# RollerShutterNode_nrf.net
KiCad netlist of a schematic drawn in EAGLE
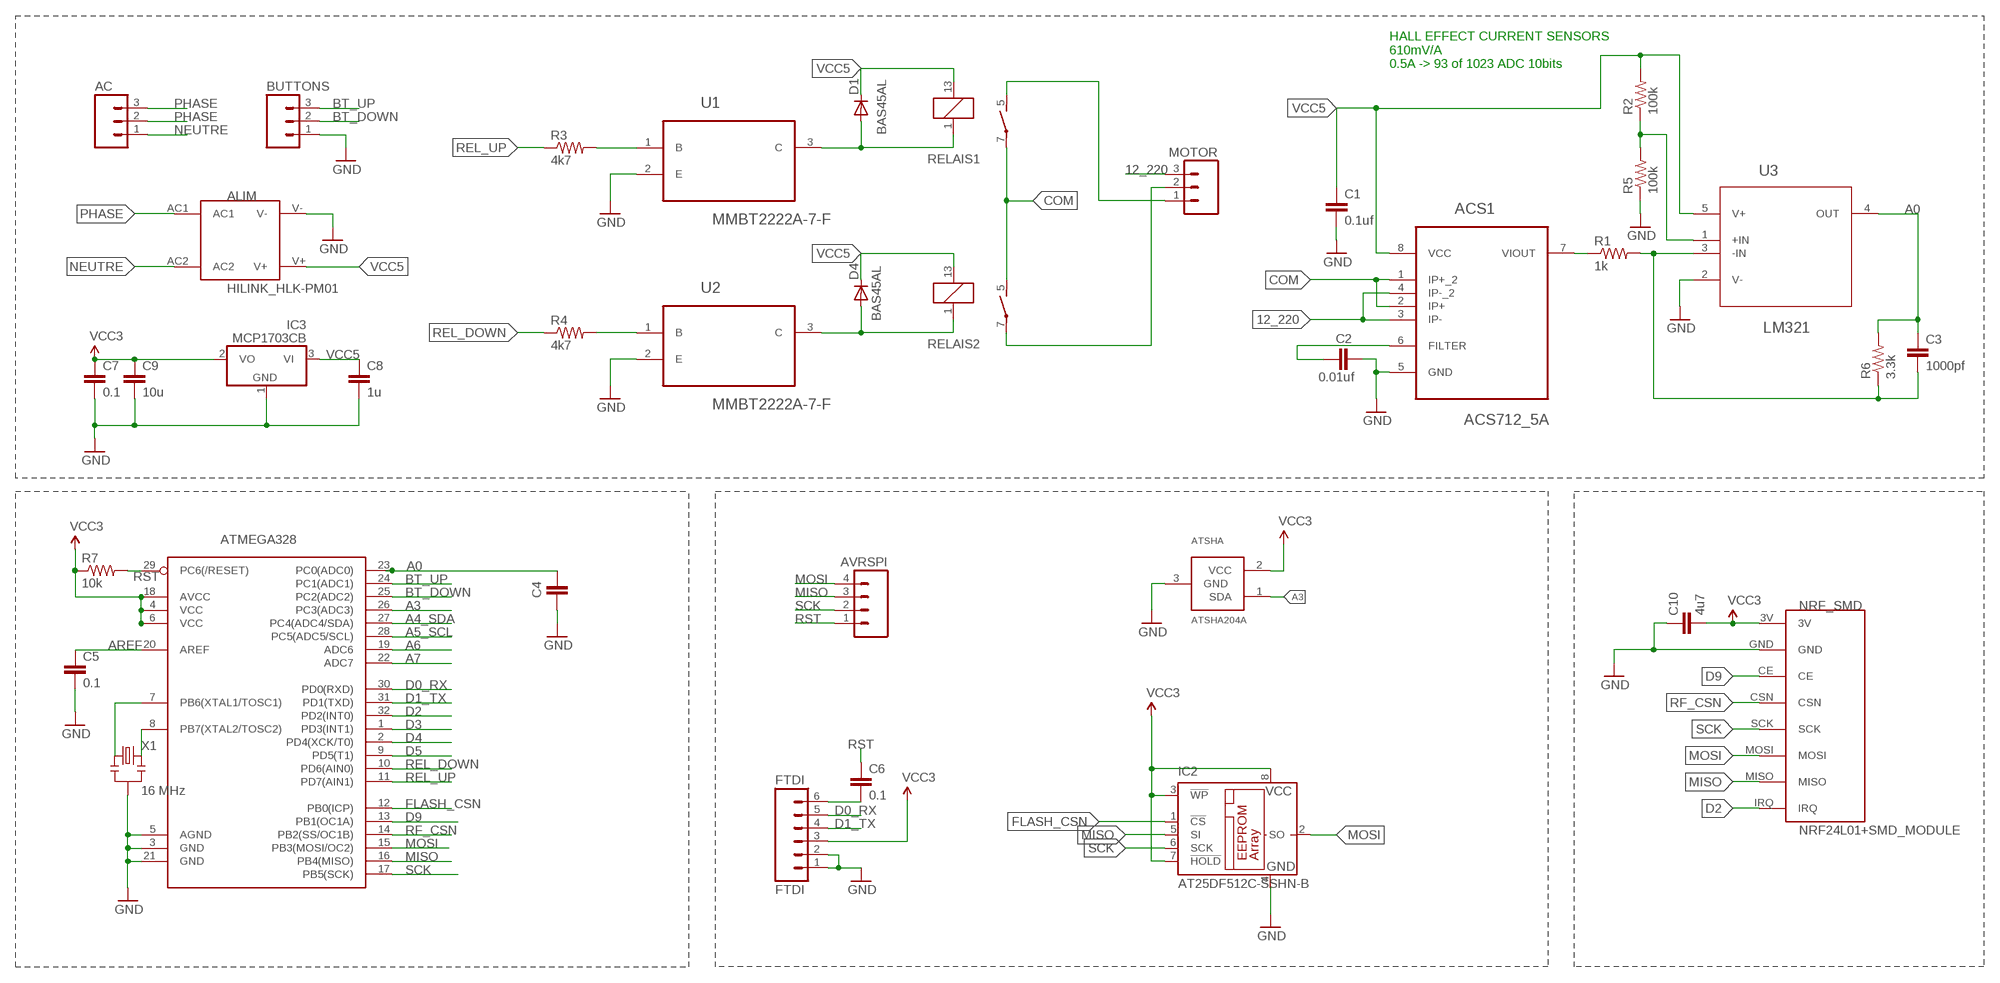
[diagram p0: schematic, sheet 1]

(export (version "E")
  (design (tool "Eeschema 10.0.6"))
  (components
    (comp (ref "AC")
      (value "M03SCREW")
      (footprint "eagle-import:SCREWTERMINAL-3.5MM-3")
      (libsource (lib "eagle-import") (part "M03SCREW"))
    )
    (comp (ref "ACS1")
      (value "ACS712_5A")
      (footprint "eagle-import:SOIC127P600X175-8N")
      (fields (field (name "MPN") "ACS712ELCTR-20A-T"))
      (libsource (lib "eagle-import") (part "ACS712ELCTR-20A-T"))
    )
    (comp (ref "ALIM")
      (value "HILINK_HLK-PM01")
      (footprint "eagle-import:HILINK_HLK-PM01")
      (libsource (lib "eagle-import") (part "HILINK_HLK-PM01"))
    )
    (comp (ref "ATMEGA328")
      (value "ATMega-328")
      (footprint "eagle-import:TQFP32-08")
      (libsource (lib "eagle-import") (part "ATMEGA168/328TQFP32"))
    )
    (comp (ref "ATSHA")
      (value "ATSHA204A")
      (footprint "eagle-import:SOT23")
      (libsource (lib "eagle-import") (part "ATSHA204A"))
    )
    (comp (ref "AVRSPI")
      (value "M04PTH")
      (footprint "eagle-import:1X04")
      (libsource (lib "eagle-import") (part "M04PTH"))
    )
    (comp (ref "BUTTONS")
      (value "M03SCREW")
      (footprint "eagle-import:SCREWTERMINAL-3.5MM-3")
      (libsource (lib "eagle-import") (part "M03SCREW"))
    )
    (comp (ref "C1")
      (value "0.1uf")
      (footprint "eagle-import:0805")
      (libsource (lib "eagle-import") (part "SparkFun-Passives_CAP0805"))
    )
    (comp (ref "C2")
      (value "0.01uf")
      (footprint "eagle-import:0805")
      (libsource (lib "eagle-import") (part "SparkFun-Passives_CAP0805"))
    )
    (comp (ref "C3")
      (value "1000pf")
      (footprint "eagle-import:0805")
      (libsource (lib "eagle-import") (part "SparkFun-Passives_CAP0805"))
    )
    (comp (ref "C4")
      (value "CAP0805")
      (footprint "eagle-import:0805")
      (libsource (lib "eagle-import") (part "SparkFun-Passives_CAP0805"))
    )
    (comp (ref "C5")
      (value "0.1")
      (footprint "eagle-import:0805")
      (libsource (lib "eagle-import") (part "CAP0805"))
    )
    (comp (ref "C6")
      (value "0.1")
      (footprint "eagle-import:0805")
      (libsource (lib "eagle-import") (part "CAP0805"))
    )
    (comp (ref "C7")
      (value "0.1")
      (footprint "eagle-import:0805")
      (libsource (lib "eagle-import") (part "CAP0805"))
    )
    (comp (ref "C8")
      (value "1u")
      (footprint "eagle-import:0805")
      (libsource (lib "eagle-import") (part "CAP0805"))
    )
    (comp (ref "C9")
      (value "10u")
      (footprint "eagle-import:0805-CAP")
      (libsource (lib "eagle-import") (part "CAP0805-CAP"))
    )
    (comp (ref "C10")
      (value "4u7")
      (footprint "eagle-import:0805")
      (libsource (lib "eagle-import") (part "SparkFun-Capacitors_CAP0805"))
    )
    (comp (ref "D1")
      (value "BAS45AL")
      (footprint "eagle-import:SOD80C")
      (libsource (lib "eagle-import") (part "DIODE-SOD80C"))
    )
    (comp (ref "D4")
      (value "BAS45AL")
      (footprint "eagle-import:SOD80C")
      (libsource (lib "eagle-import") (part "DIODE-SOD80C"))
    )
    (comp (ref "FTDI")
      (value "FTDI")
      (footprint "eagle-import:1X06")
      (libsource (lib "eagle-import") (part "M06SIP"))
    )
    (comp (ref "IC2")
      (value "AT25DF512C-SSHN-B")
      (footprint "eagle-import:SO-08")
      (fields (field (name "MF") "MICROCHIP") (field (name "MPN") "25AA080/SN"))
      (libsource (lib "eagle-import") (part "25SNAA080"))
    )
    (comp (ref "IC3")
      (value "MCP1703CB")
      (footprint "eagle-import:SOT23")
      (libsource (lib "eagle-import") (part "MCP1703CB"))
    )
    (comp (ref "MOTOR")
      (value "M03SCREW")
      (footprint "eagle-import:SCREWTERMINAL-3.5MM-3")
      (libsource (lib "eagle-import") (part "M03SCREW"))
    )
    (comp (ref "NRF_SMD")
      (value "NRF24L01+SMD_MODULE")
      (footprint "eagle-import:NRF24L01+SMD_MODULE")
      (libsource (lib "eagle-import") (part "NRF24L01+SMD_MODULE"))
    )
    (comp (ref "R1")
      (value "1k")
      (footprint "eagle-import:0805")
      (libsource (lib "eagle-import") (part "SparkFun-Resistors_RESISTOR0805-RES"))
    )
    (comp (ref "R2")
      (value "100k")
      (footprint "eagle-import:0805")
      (libsource (lib "eagle-import") (part "SparkFun-Resistors_RESISTOR0805-RES"))
    )
    (comp (ref "R3")
      (value "4k7")
      (footprint "eagle-import:0805")
      (libsource (lib "eagle-import") (part "SparkFun-Resistors_RESISTOR0805-RES"))
    )
    (comp (ref "R4")
      (value "4k7")
      (footprint "eagle-import:0805")
      (libsource (lib "eagle-import") (part "SparkFun-Resistors_RESISTOR0805-RES"))
    )
    (comp (ref "R5")
      (value "100k")
      (footprint "eagle-import:0805")
      (libsource (lib "eagle-import") (part "SparkFun-Resistors_RESISTOR0805-RES"))
    )
    (comp (ref "R6")
      (value "3.3k")
      (footprint "eagle-import:0805")
      (libsource (lib "eagle-import") (part "SparkFun-Resistors_RESISTOR0805-RES"))
    )
    (comp (ref "R7")
      (value "10k")
      (footprint "eagle-import:0805")
      (libsource (lib "eagle-import") (part "RESISTOR0805"))
    )
    (comp (ref "RELAIS1")
      (value "Relais G6D")
      (footprint "eagle-import:G6D")
      (libsource (lib "eagle-import") (part "G6D?-1A-ASI12VDC"))
    )
    (comp (ref "RELAIS2")
      (value "Relais G6D")
      (footprint "eagle-import:G6D")
      (libsource (lib "eagle-import") (part "G6D?-1A-ASI12VDC"))
    )
    (comp (ref "U1")
      (value "MMBT2222A-7-F")
      (footprint "eagle-import:SOT103P240X110-3N")
      (libsource (lib "eagle-import") (part "MMBT2222A-7-F"))
    )
    (comp (ref "U2")
      (value "MMBT2222A-7-F")
      (footprint "eagle-import:SOT103P240X110-3N")
      (libsource (lib "eagle-import") (part "MMBT2222A-7-F"))
    )
    (comp (ref "U3")
      (value "LM321")
      (footprint "eagle-import:SOT95P285X120-5N")
      (fields (field (name "MPN") "LM321MF"))
      (libsource (lib "eagle-import") (part "LM321MF"))
    )
    (comp (ref "X1")
      (value "16 MHz")
      (footprint "eagle-import:RESONATOR-SMD")
      (libsource (lib "eagle-import") (part "RESONATORSMD"))
    )
  )
  (nets
    (net (code "1") (name "/A0") (class "Default")
      (node (ref "ATMEGA328") (pin "23") (pinfunction "PC0(ADC0)_23") (pintype "bidirectional"))
      (node (ref "C3") (pin "1") (pinfunction "1_1") (pintype "passive"))
      (node (ref "C4") (pin "2") (pinfunction "2_2") (pintype "passive"))
      (node (ref "R6") (pin "2") (pinfunction "2_2") (pintype "passive"))
      (node (ref "U3") (pin "4") (pinfunction "OUT_4") (pintype "output"))
    )
    (net (code "2") (name "/A4_SDA") (class "Default")
      (node (ref "ATMEGA328") (pin "27") (pinfunction "PC4(ADC4/SDA)_27") (pintype "bidirectional"))
    )
    (net (code "3") (name "/A5_SCL") (class "Default")
      (node (ref "ATMEGA328") (pin "28") (pinfunction "PC5(ADC5/SCL)_28") (pintype "bidirectional"))
    )
    (net (code "4") (name "/A6") (class "Default")
      (node (ref "ATMEGA328") (pin "19") (pinfunction "ADC6_19") (pintype "bidirectional"))
    )
    (net (code "5") (name "/A7") (class "Default")
      (node (ref "ATMEGA328") (pin "22") (pinfunction "ADC7_22") (pintype "bidirectional"))
    )
    (net (code "6") (name "/AREF") (class "Default")
      (node (ref "ATMEGA328") (pin "20") (pinfunction "AREF_20") (pintype "bidirectional"))
      (node (ref "C5") (pin "1") (pinfunction "1_1") (pintype "passive"))
    )
    (net (code "7") (name "/BT_DOWN") (class "Default")
      (node (ref "ATMEGA328") (pin "25") (pinfunction "PC2(ADC2)_25") (pintype "bidirectional"))
      (node (ref "BUTTONS") (pin "2") (pinfunction "2_2") (pintype "passive"))
    )
    (net (code "8") (name "/BT_UP") (class "Default")
      (node (ref "ATMEGA328") (pin "24") (pinfunction "PC1(ADC1)_24") (pintype "bidirectional"))
      (node (ref "BUTTONS") (pin "3") (pinfunction "3_3") (pintype "passive"))
    )
    (net (code "9") (name "/D0_RX") (class "Default")
      (node (ref "ATMEGA328") (pin "30") (pinfunction "PD0(RXD)_30") (pintype "bidirectional"))
      (node (ref "FTDI") (pin "5") (pinfunction "5_5") (pintype "passive"))
    )
    (net (code "10") (name "/D1_TX") (class "Default")
      (node (ref "ATMEGA328") (pin "31") (pinfunction "PD1(TXD)_31") (pintype "bidirectional"))
      (node (ref "FTDI") (pin "4") (pinfunction "4_4") (pintype "passive"))
    )
    (net (code "11") (name "/D3") (class "Default")
      (node (ref "ATMEGA328") (pin "1") (pinfunction "PD3(INT1)_1") (pintype "bidirectional"))
    )
    (net (code "12") (name "/D4") (class "Default")
      (node (ref "ATMEGA328") (pin "2") (pinfunction "PD4(XCK/T0)_2") (pintype "bidirectional"))
    )
    (net (code "13") (name "/D5") (class "Default")
      (node (ref "ATMEGA328") (pin "9") (pinfunction "PD5(T1)_9") (pintype "bidirectional"))
    )
    (net (code "14") (name "/RST") (class "Default")
      (node (ref "ATMEGA328") (pin "29") (pinfunction "PC6(/RESET)_29") (pintype "bidirectional"))
      (node (ref "AVRSPI") (pin "1") (pinfunction "1_1") (pintype "passive"))
      (node (ref "C6") (pin "1") (pinfunction "1_1") (pintype "passive"))
      (node (ref "R7") (pin "2") (pinfunction "2_2") (pintype "passive"))
    )
    (net (code "15") (name "12_220") (class "Default")
      (node (ref "ACS1") (pin "3") (pinfunction "IP-_3") (pintype "input"))
      (node (ref "ACS1") (pin "4") (pinfunction "IP-_2_4") (pintype "input"))
      (node (ref "MOTOR") (pin "3") (pinfunction "3_3") (pintype "passive"))
    )
    (net (code "16") (name "A3") (class "Default")
      (node (ref "ATMEGA328") (pin "26") (pinfunction "PC3(ADC3)_26") (pintype "bidirectional"))
      (node (ref "ATSHA") (pin "1") (pinfunction "SDA_1") (pintype "bidirectional"))
    )
    (net (code "17") (name "COM") (class "Default")
      (node (ref "ACS1") (pin "1") (pinfunction "IP+_2_1") (pintype "input"))
      (node (ref "ACS1") (pin "2") (pinfunction "IP+_2") (pintype "input"))
      (node (ref "RELAIS1") (pin "7") (pinfunction "P_7") (pintype "passive"))
      (node (ref "RELAIS2") (pin "5") (pinfunction "S_5") (pintype "passive"))
    )
    (net (code "18") (name "D2") (class "Default")
      (node (ref "ATMEGA328") (pin "32") (pinfunction "PD2(INT0)_32") (pintype "bidirectional"))
      (node (ref "NRF_SMD") (pin "IRQ") (pinfunction "IRQ_IRQ") (pintype "bidirectional"))
    )
    (net (code "19") (name "D9") (class "Default")
      (node (ref "ATMEGA328") (pin "13") (pinfunction "PB1(OC1A)_13") (pintype "bidirectional"))
      (node (ref "NRF_SMD") (pin "CE") (pinfunction "CE_CE") (pintype "bidirectional"))
    )
    (net (code "20") (name "FLASH_CSN") (class "Default")
      (node (ref "ATMEGA328") (pin "12") (pinfunction "PB0(ICP)_12") (pintype "bidirectional"))
      (node (ref "IC2") (pin "1") (pinfunction "~{CS}_1") (pintype "input"))
    )
    (net (code "21") (name "GND") (class "Default")
      (node (ref "ACS1") (pin "5") (pinfunction "GND_5") (pintype "passive"))
      (node (ref "ALIM") (pin "V-") (pinfunction "V-_V-") (pintype "bidirectional"))
      (node (ref "ATMEGA328") (pin "21") (pinfunction "GND_21") (pintype "bidirectional"))
      (node (ref "ATMEGA328") (pin "3") (pinfunction "GND_3") (pintype "bidirectional"))
      (node (ref "ATMEGA328") (pin "5") (pinfunction "AGND_5") (pintype "bidirectional"))
      (node (ref "ATSHA") (pin "3") (pinfunction "GND_3") (pintype "bidirectional"))
      (node (ref "BUTTONS") (pin "1") (pinfunction "1_1") (pintype "passive"))
      (node (ref "C1") (pin "2") (pinfunction "2_2") (pintype "passive"))
      (node (ref "C10") (pin "1") (pinfunction "1_1") (pintype "passive"))
      (node (ref "C2") (pin "2") (pinfunction "2_2") (pintype "passive"))
      (node (ref "C4") (pin "1") (pinfunction "1_1") (pintype "passive"))
      (node (ref "C5") (pin "2") (pinfunction "2_2") (pintype "passive"))
      (node (ref "C7") (pin "2") (pinfunction "2_2") (pintype "passive"))
      (node (ref "C8") (pin "2") (pinfunction "2_2") (pintype "passive"))
      (node (ref "C9") (pin "2") (pinfunction "2_2") (pintype "passive"))
      (node (ref "FTDI") (pin "1") (pinfunction "1_1") (pintype "passive"))
      (node (ref "FTDI") (pin "2") (pinfunction "2_2") (pintype "passive"))
      (node (ref "IC2") (pin "4") (pinfunction "GND_4") (pintype "power_in"))
      (node (ref "IC3") (pin "1") (pinfunction "GND_1") (pintype "passive"))
      (node (ref "NRF_SMD") (pin "GND") (pinfunction "GND_GND") (pintype "bidirectional"))
      (node (ref "R5") (pin "1") (pinfunction "1_1") (pintype "passive"))
      (node (ref "U1") (pin "2") (pinfunction "E_2") (pintype "passive"))
      (node (ref "U2") (pin "2") (pinfunction "E_2") (pintype "passive"))
      (node (ref "U3") (pin "2") (pinfunction "V-_2") (pintype "power_in"))
      (node (ref "X1") (pin "2") (pinfunction "2_2") (pintype "passive"))
    )
    (net (code "22") (name "MISO") (class "Default")
      (node (ref "ATMEGA328") (pin "16") (pinfunction "PB4(MISO)_16") (pintype "bidirectional"))
      (node (ref "AVRSPI") (pin "3") (pinfunction "3_3") (pintype "passive"))
      (node (ref "IC2") (pin "5") (pinfunction "SI_5") (pintype "input"))
      (node (ref "NRF_SMD") (pin "MISO") (pinfunction "MISO_MISO") (pintype "bidirectional"))
    )
    (net (code "23") (name "MOSI") (class "Default")
      (node (ref "ATMEGA328") (pin "15") (pinfunction "PB3(MOSI/OC2)_15") (pintype "bidirectional"))
      (node (ref "AVRSPI") (pin "4") (pinfunction "4_4") (pintype "passive"))
      (node (ref "IC2") (pin "2") (pinfunction "SO_2") (pintype "bidirectional"))
      (node (ref "NRF_SMD") (pin "MOSI") (pinfunction "MOSI_MOSI") (pintype "bidirectional"))
    )
    (net (code "24") (name "NEUTRE") (class "Default")
      (node (ref "AC") (pin "1") (pinfunction "1_1") (pintype "passive"))
      (node (ref "ALIM") (pin "AC2") (pinfunction "AC2_AC2") (pintype "bidirectional"))
    )
    (net (code "25") (name "Net-(ACS1-FILTER)") (class "Default")
      (node (ref "ACS1") (pin "6") (pinfunction "FILTER_6") (pintype "input"))
      (node (ref "C2") (pin "1") (pinfunction "1_1") (pintype "passive"))
    )
    (net (code "26") (name "Net-(ACS1-VIOUT)") (class "Default")
      (node (ref "ACS1") (pin "7") (pinfunction "VIOUT_7") (pintype "output"))
      (node (ref "R1") (pin "1") (pinfunction "1_1") (pintype "passive"))
    )
    (net (code "27") (name "Net-(ATMEGA328-PB6(XTAL1{slash}TOSC1))") (class "Default")
      (node (ref "ATMEGA328") (pin "7") (pinfunction "PB6(XTAL1/TOSC1)_7") (pintype "bidirectional"))
      (node (ref "X1") (pin "1") (pinfunction "1_1") (pintype "passive"))
    )
    (net (code "28") (name "Net-(ATMEGA328-PB7(XTAL2{slash}TOSC2))") (class "Default")
      (node (ref "ATMEGA328") (pin "8") (pinfunction "PB7(XTAL2/TOSC2)_8") (pintype "bidirectional"))
      (node (ref "X1") (pin "3") (pinfunction "3_3") (pintype "passive"))
    )
    (net (code "29") (name "Net-(C6-Pad2)") (class "Default")
      (node (ref "C6") (pin "2") (pinfunction "2_2") (pintype "passive"))
      (node (ref "FTDI") (pin "6") (pinfunction "6_6") (pintype "passive"))
    )
    (net (code "30") (name "Net-(RELAIS1B-S)") (class "Default")
      (node (ref "MOTOR") (pin "1") (pinfunction "1_1") (pintype "passive"))
      (node (ref "RELAIS1") (pin "5") (pinfunction "S_5") (pintype "passive"))
    )
    (net (code "31") (name "Net-(RELAIS2B-P)") (class "Default")
      (node (ref "MOTOR") (pin "2") (pinfunction "2_2") (pintype "passive"))
      (node (ref "RELAIS2") (pin "7") (pinfunction "P_7") (pintype "passive"))
    )
    (net (code "32") (name "Net-(U1-B)") (class "Default")
      (node (ref "R3") (pin "2") (pinfunction "2_2") (pintype "passive"))
      (node (ref "U1") (pin "1") (pinfunction "B_1") (pintype "input"))
    )
    (net (code "33") (name "Net-(U1-C)") (class "Default")
      (node (ref "D1") (pin "A") (pinfunction "A_A") (pintype "passive"))
      (node (ref "RELAIS1") (pin "1") (pinfunction "1_1") (pintype "passive"))
      (node (ref "U1") (pin "3") (pinfunction "C_3") (pintype "output"))
    )
    (net (code "34") (name "Net-(U2-B)") (class "Default")
      (node (ref "R4") (pin "2") (pinfunction "2_2") (pintype "passive"))
      (node (ref "U2") (pin "1") (pinfunction "B_1") (pintype "input"))
    )
    (net (code "35") (name "Net-(U2-C)") (class "Default")
      (node (ref "D4") (pin "A") (pinfunction "A_A") (pintype "passive"))
      (node (ref "RELAIS2") (pin "1") (pinfunction "1_1") (pintype "passive"))
      (node (ref "U2") (pin "3") (pinfunction "C_3") (pintype "output"))
    )
    (net (code "36") (name "Net-(U3-+IN)") (class "Default")
      (node (ref "R2") (pin "1") (pinfunction "1_1") (pintype "passive"))
      (node (ref "R5") (pin "2") (pinfunction "2_2") (pintype "passive"))
      (node (ref "U3") (pin "1") (pinfunction "+IN_1") (pintype "input"))
    )
    (net (code "37") (name "Net-(U3--IN)") (class "Default")
      (node (ref "C3") (pin "2") (pinfunction "2_2") (pintype "passive"))
      (node (ref "R1") (pin "2") (pinfunction "2_2") (pintype "passive"))
      (node (ref "R6") (pin "1") (pinfunction "1_1") (pintype "passive"))
      (node (ref "U3") (pin "3") (pinfunction "-IN_3") (pintype "input"))
    )
    (net (code "38") (name "PHASE") (class "Default")
      (node (ref "AC") (pin "2") (pinfunction "2_2") (pintype "passive"))
      (node (ref "AC") (pin "3") (pinfunction "3_3") (pintype "passive"))
      (node (ref "ALIM") (pin "AC1") (pinfunction "AC1_AC1") (pintype "bidirectional"))
    )
    (net (code "39") (name "REL_DOWN") (class "Default")
      (node (ref "ATMEGA328") (pin "10") (pinfunction "PD6(AIN0)_10") (pintype "bidirectional"))
      (node (ref "R4") (pin "1") (pinfunction "1_1") (pintype "passive"))
    )
    (net (code "40") (name "REL_UP") (class "Default")
      (node (ref "ATMEGA328") (pin "11") (pinfunction "PD7(AIN1)_11") (pintype "bidirectional"))
      (node (ref "R3") (pin "1") (pinfunction "1_1") (pintype "passive"))
    )
    (net (code "41") (name "RF_CSN") (class "Default")
      (node (ref "ATMEGA328") (pin "14") (pinfunction "PB2(SS/OC1B)_14") (pintype "bidirectional"))
      (node (ref "NRF_SMD") (pin "CSN") (pinfunction "CSN_CSN") (pintype "bidirectional"))
    )
    (net (code "42") (name "SCK") (class "Default")
      (node (ref "ATMEGA328") (pin "17") (pinfunction "PB5(SCK)_17") (pintype "bidirectional"))
      (node (ref "AVRSPI") (pin "2") (pinfunction "2_2") (pintype "passive"))
      (node (ref "IC2") (pin "6") (pinfunction "SCK_6") (pintype "input"))
      (node (ref "NRF_SMD") (pin "SCK") (pinfunction "SCK_SCK") (pintype "bidirectional"))
    )
    (net (code "43") (name "VCC3") (class "Default")
      (node (ref "ATMEGA328") (pin "18") (pinfunction "AVCC_18") (pintype "bidirectional"))
      (node (ref "ATMEGA328") (pin "4") (pinfunction "VCC_4") (pintype "bidirectional"))
      (node (ref "ATMEGA328") (pin "6") (pinfunction "VCC_6") (pintype "bidirectional"))
      (node (ref "ATSHA") (pin "2") (pinfunction "VCC_2") (pintype "bidirectional"))
      (node (ref "C10") (pin "2") (pinfunction "2_2") (pintype "passive"))
      (node (ref "C7") (pin "1") (pinfunction "1_1") (pintype "passive"))
      (node (ref "C9") (pin "1") (pinfunction "1_1") (pintype "passive"))
      (node (ref "FTDI") (pin "3") (pinfunction "3_3") (pintype "passive"))
      (node (ref "IC2") (pin "3") (pinfunction "~{WP}_3") (pintype "input"))
      (node (ref "IC2") (pin "7") (pinfunction "~{HOLD}_7") (pintype "input"))
      (node (ref "IC2") (pin "8") (pinfunction "VCC_8") (pintype "power_in"))
      (node (ref "IC3") (pin "2") (pinfunction "VO_2") (pintype "passive"))
      (node (ref "NRF_SMD") (pin "3V") (pinfunction "3V_3V") (pintype "bidirectional"))
      (node (ref "R7") (pin "1") (pinfunction "1_1") (pintype "passive"))
    )
    (net (code "44") (name "VCC5") (class "Default")
      (node (ref "ACS1") (pin "8") (pinfunction "VCC_8") (pintype "power_in"))
      (node (ref "ALIM") (pin "V+") (pinfunction "V+_V+") (pintype "bidirectional"))
      (node (ref "C1") (pin "1") (pinfunction "1_1") (pintype "passive"))
      (node (ref "C8") (pin "1") (pinfunction "1_1") (pintype "passive"))
      (node (ref "D1") (pin "C") (pinfunction "C_C") (pintype "passive"))
      (node (ref "D4") (pin "C") (pinfunction "C_C") (pintype "passive"))
      (node (ref "IC3") (pin "3") (pinfunction "VI_3") (pintype "input"))
      (node (ref "R2") (pin "2") (pinfunction "2_2") (pintype "passive"))
      (node (ref "RELAIS1") (pin "13") (pinfunction "2_13") (pintype "passive"))
      (node (ref "RELAIS2") (pin "13") (pinfunction "2_13") (pintype "passive"))
      (node (ref "U3") (pin "5") (pinfunction "V+_5") (pintype "power_in"))
    )
  )
)
